# EM2050.net
KiCad netlist of a schematic drawn in Altium Designer
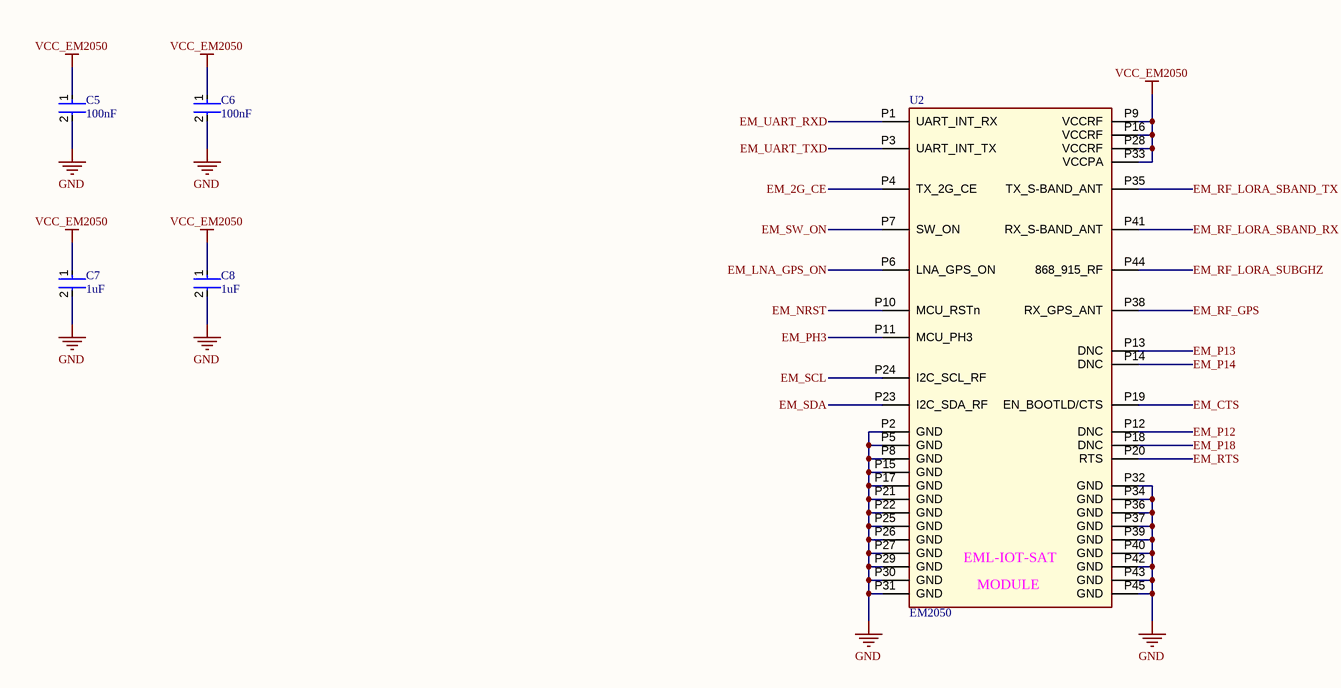
[diagram p0: EM2050.SchDoc]

(export (version "E")
  (design (tool "Eeschema 10.0.6"))
  (components
    (comp (ref "C5")
      (value "0402ZD104KAT2A")
      (footprint "FP-0402-L_1_0_1-W_0_5_0_1-IPC_C")
      (description "General Purpose Ceramic Capacitor, 0402, 100nF, 10%, X5R, 15%, 10V")
      (fields
        (field (name "VOLTAGE") "10V")
        (field (name "TOLERANCE") "10%")
        (field (name "CAPACITANCE") "100nF")
      )
      (libsource (lib "ApolloEcho_Dev_Kit") (part "b4654b650e69147ec39a6b967a45e02"))
    )
    (comp (ref "C6")
      (value "0402ZD104KAT2A")
      (footprint "FP-0402-L_1_0_1-W_0_5_0_1-IPC_C")
      (description "General Purpose Ceramic Capacitor, 0402, 100nF, 10%, X5R, 15%, 10V")
      (fields
        (field (name "VOLTAGE") "10V")
        (field (name "TOLERANCE") "10%")
        (field (name "CAPACITANCE") "100nF")
      )
      (libsource (lib "ApolloEcho_Dev_Kit") (part "b4654b650e69147ec39a6b967a45e02"))
    )
    (comp (ref "C7")
      (value "EMK105BJ105KV-F")
      (footprint "FP-0402-L_1_0_0_05-W_0_5-IPC_A")
      (description "None")
      (fields (field (name "TOLERANCE") "10%") (field (name "CAPACITANCE") "1uF"))
      (libsource (lib "ApolloEcho_Dev_Kit") (part "b4654b650e69147ec39a6b967a45e02"))
    )
    (comp (ref "C8")
      (value "EMK105BJ105KV-F")
      (footprint "FP-0402-L_1_0_0_05-W_0_5-IPC_A")
      (description "None")
      (fields (field (name "TOLERANCE") "10%") (field (name "CAPACITANCE") "1uF"))
      (libsource (lib "ApolloEcho_Dev_Kit") (part "b4654b650e69147ec39a6b967a45e02"))
    )
    (comp (ref "U2")
      (value "EM2050")
      (footprint "EM2050")
      (description "Echostar Mobile IOT SAT Module - Basic version")
      (fields (field (name "MANUFACTURER") "Echostar Mobile Ltd") (field (name "Comment") "IOT SAT module"))
      (libsource (lib "ApolloEcho_Dev_Kit") (part "EM2050"))
    )
  )
  (nets
    (net (code "1") (name "/EM_2G_CE") (class "Default")
      (node (ref "U2") (pin "P4") (pinfunction "TX_2G_CE_P4") (pintype "passive"))
    )
    (net (code "2") (name "/EM_CTS") (class "Default")
      (node (ref "U2") (pin "P19") (pinfunction "EN_BOOTLD/CTS_P19") (pintype "passive"))
    )
    (net (code "3") (name "/EM_LNA_GPS_ON") (class "Default")
      (node (ref "U2") (pin "P6") (pinfunction "LNA_GPS_ON_P6") (pintype "passive"))
    )
    (net (code "4") (name "/EM_NRST") (class "Default")
      (node (ref "U2") (pin "P10") (pinfunction "MCU_RSTn_P10") (pintype "passive"))
    )
    (net (code "5") (name "/EM_P12") (class "Default")
      (node (ref "U2") (pin "P12") (pinfunction "DNC_P12") (pintype "passive"))
    )
    (net (code "6") (name "/EM_P13") (class "Default")
      (node (ref "U2") (pin "P13") (pinfunction "DNC_P13") (pintype "passive"))
    )
    (net (code "7") (name "/EM_P14") (class "Default")
      (node (ref "U2") (pin "P14") (pinfunction "DNC_P14") (pintype "passive"))
    )
    (net (code "8") (name "/EM_P18") (class "Default")
      (node (ref "U2") (pin "P18") (pinfunction "DNC_P18") (pintype "passive"))
    )
    (net (code "9") (name "/EM_PH3") (class "Default")
      (node (ref "U2") (pin "P11") (pinfunction "MCU_PH3_P11") (pintype "passive"))
    )
    (net (code "10") (name "/EM_RF_GPS") (class "Default")
      (node (ref "U2") (pin "P38") (pinfunction "RX_GPS_ANT_P38") (pintype "passive"))
    )
    (net (code "11") (name "/EM_RF_LORA_SBAND_RX") (class "Default")
      (node (ref "U2") (pin "P41") (pinfunction "RX_S-BAND_ANT_P41") (pintype "passive"))
    )
    (net (code "12") (name "/EM_RF_LORA_SBAND_TX") (class "Default")
      (node (ref "U2") (pin "P35") (pinfunction "TX_S-BAND_ANT_P35") (pintype "passive"))
    )
    (net (code "13") (name "/EM_RF_LORA_SUBGHZ") (class "Default")
      (node (ref "U2") (pin "P44") (pinfunction "868_915_RF_P44") (pintype "passive"))
    )
    (net (code "14") (name "/EM_RTS") (class "Default")
      (node (ref "U2") (pin "P20") (pinfunction "RTS_P20") (pintype "passive"))
    )
    (net (code "15") (name "/EM_SCL") (class "Default")
      (node (ref "U2") (pin "P24") (pinfunction "I2C_SCL_RF_P24") (pintype "passive"))
    )
    (net (code "16") (name "/EM_SDA") (class "Default")
      (node (ref "U2") (pin "P23") (pinfunction "I2C_SDA_RF_P23") (pintype "passive"))
    )
    (net (code "17") (name "/EM_SW_ON") (class "Default")
      (node (ref "U2") (pin "P7") (pinfunction "SW_ON_P7") (pintype "passive"))
    )
    (net (code "18") (name "/EM_UART_RXD") (class "Default")
      (node (ref "U2") (pin "P1") (pinfunction "UART_INT_RX_P1") (pintype "passive"))
    )
    (net (code "19") (name "/EM_UART_TXD") (class "Default")
      (node (ref "U2") (pin "P3") (pinfunction "UART_INT_TX_P3") (pintype "passive"))
    )
    (net (code "20") (name "GND") (class "Default")
      (node (ref "C5") (pin "2") (pinfunction "2_2") (pintype "passive"))
      (node (ref "C6") (pin "2") (pinfunction "2_2") (pintype "passive"))
      (node (ref "C7") (pin "2") (pinfunction "2_2") (pintype "passive"))
      (node (ref "C8") (pin "2") (pinfunction "2_2") (pintype "passive"))
      (node (ref "U2") (pin "P15") (pinfunction "GND_P15") (pintype "passive"))
      (node (ref "U2") (pin "P17") (pinfunction "GND_P17") (pintype "passive"))
      (node (ref "U2") (pin "P2") (pinfunction "GND_P2") (pintype "passive"))
      (node (ref "U2") (pin "P21") (pinfunction "GND_P21") (pintype "passive"))
      (node (ref "U2") (pin "P22") (pinfunction "GND_P22") (pintype "passive"))
      (node (ref "U2") (pin "P25") (pinfunction "GND_P25") (pintype "passive"))
      (node (ref "U2") (pin "P26") (pinfunction "GND_P26") (pintype "passive"))
      (node (ref "U2") (pin "P27") (pinfunction "GND_P27") (pintype "passive"))
      (node (ref "U2") (pin "P29") (pinfunction "GND_P29") (pintype "passive"))
      (node (ref "U2") (pin "P30") (pinfunction "GND_P30") (pintype "passive"))
      (node (ref "U2") (pin "P31") (pinfunction "GND_P31") (pintype "passive"))
      (node (ref "U2") (pin "P32") (pinfunction "GND_P32") (pintype "passive"))
      (node (ref "U2") (pin "P34") (pinfunction "GND_P34") (pintype "passive"))
      (node (ref "U2") (pin "P36") (pinfunction "GND_P36") (pintype "passive"))
      (node (ref "U2") (pin "P37") (pinfunction "GND_P37") (pintype "passive"))
      (node (ref "U2") (pin "P39") (pinfunction "GND_P39") (pintype "passive"))
      (node (ref "U2") (pin "P40") (pinfunction "GND_P40") (pintype "passive"))
      (node (ref "U2") (pin "P42") (pinfunction "GND_P42") (pintype "passive"))
      (node (ref "U2") (pin "P43") (pinfunction "GND_P43") (pintype "passive"))
      (node (ref "U2") (pin "P45") (pinfunction "GND_P45") (pintype "passive"))
      (node (ref "U2") (pin "P5") (pinfunction "GND_P5") (pintype "passive"))
      (node (ref "U2") (pin "P8") (pinfunction "GND_P8") (pintype "passive"))
    )
    (net (code "21") (name "VCC_EM2050") (class "Default")
      (node (ref "C5") (pin "1") (pinfunction "1_1") (pintype "passive"))
      (node (ref "C6") (pin "1") (pinfunction "1_1") (pintype "passive"))
      (node (ref "C7") (pin "1") (pinfunction "1_1") (pintype "passive"))
      (node (ref "C8") (pin "1") (pinfunction "1_1") (pintype "passive"))
      (node (ref "U2") (pin "P16") (pinfunction "VCCRF_P16") (pintype "passive"))
      (node (ref "U2") (pin "P28") (pinfunction "VCCRF_P28") (pintype "passive"))
      (node (ref "U2") (pin "P33") (pinfunction "VCCPA_P33") (pintype "passive"))
      (node (ref "U2") (pin "P9") (pinfunction "VCCRF_P9") (pintype "passive"))
    )
  )
)
